# ADC.net
KiCad netlist of a schematic drawn in Altium Designer
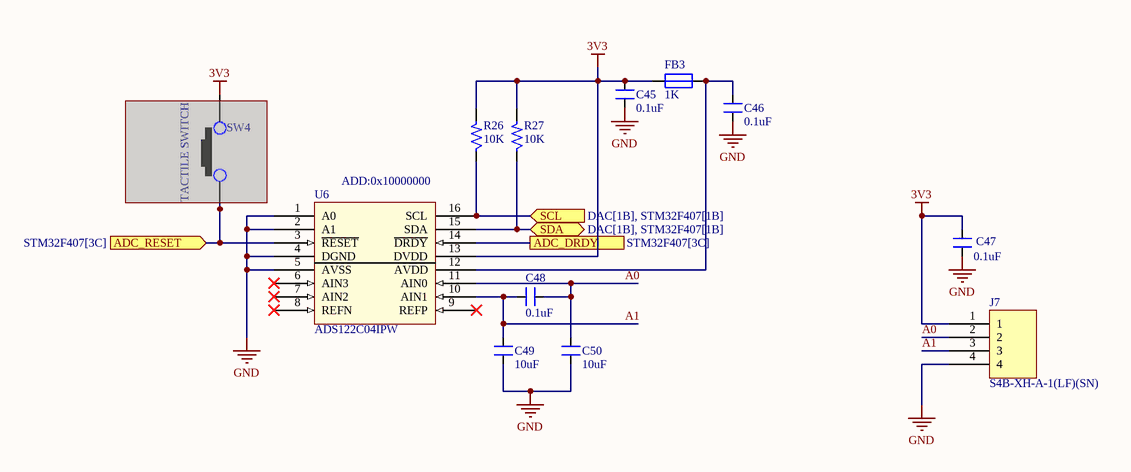
[diagram p0: ADC.SchDoc]

(export (version "E")
  (design (tool "Eeschema 10.0.6"))
  (components
    (comp (ref "C45")
      (value "0.1uF")
      (footprint "CAP_0805")
      (description "0.1µF ±10% 50V Ceramic Capacitor X7R 0805 (2012 Metric)")
      (fields
        (field (name "MANUFACTURER") "Samsung")
        (field (name "MANUFACTURER PART NUMBER") "CL21B104KBCNNNC")
      )
      (libsource (lib "ESTEEMPCBLIB") (part "CAP_0.1uF-50V-10%-0805"))
    )
    (comp (ref "C46")
      (value "0.1uF")
      (footprint "CAP_0805")
      (description "0.1µF ±10% 50V Ceramic Capacitor X7R 0805 (2012 Metric)")
      (fields
        (field (name "MANUFACTURER") "Samsung")
        (field (name "MANUFACTURER PART NUMBER") "CL21B104KBCNNNC")
      )
      (libsource (lib "ESTEEMPCBLIB") (part "CAP_0.1uF-50V-10%-0805"))
    )
    (comp (ref "C47")
      (value "0.1uF")
      (footprint "CAP_0805")
      (description "0.1µF ±10% 50V Ceramic Capacitor X7R 0805 (2012 Metric)")
      (fields
        (field (name "MANUFACTURER") "Samsung")
        (field (name "MANUFACTURER PART NUMBER") "CL21B104KBCNNNC")
      )
      (libsource (lib "ESTEEMPCBLIB") (part "CAP_0.1uF-50V-10%-0805"))
    )
    (comp (ref "C48")
      (value "0.1uF")
      (footprint "CAP_0805")
      (description "0.1µF ±5% 50V Ceramic Capacitor X7R 0805 (2012 Metric)")
      (fields
        (field (name "MANUFACTURER") "AVX Corporation")
        (field (name "MANUFACTURER PART NUMBER") "08055C104JAT4A")
      )
      (libsource (lib "ESTEEMPCBLIB") (part "CAP_0.1uF-50V-5%-0805"))
    )
    (comp (ref "C49")
      (value "10uF")
      (footprint "CAP_1206")
      (description "10µF ±10% 50V Ceramic Capacitor X7R 1206 (3216 Metric)")
      (fields
        (field (name "MANUFACTURER") "KEMET")
        (field (name "MANUFACTURER PART NUMBER") "CL31B106KBHNNNE")
      )
      (libsource (lib "ESTEEMPCBLIB") (part "CAP_10uF-50V-10%-1206"))
    )
    (comp (ref "C50")
      (value "10uF")
      (footprint "CAP_1206")
      (description "10µF ±10% 50V Ceramic Capacitor X7R 1206 (3216 Metric)")
      (fields
        (field (name "MANUFACTURER") "KEMET")
        (field (name "MANUFACTURER PART NUMBER") "CL31B106KBHNNNE")
      )
      (libsource (lib "ESTEEMPCBLIB") (part "CAP_10uF-50V-10%-1206"))
    )
    (comp (ref "FB3")
      (value "1K")
      (footprint "IND_0805")
      (description "1 kOhms @ 100MHz 1 Power Line Ferrite Bead 0805 (2012 Metric) 1.6A")
      (fields
        (field (name "MANUFACTURER") "Laird")
        (field (name "MANUFACTURER PART NUMBER") "BLM21SP102SH1D")
      )
      (libsource (lib "ESTEEMPCBLIB") (part "FB_1K-100MHZ-1.6A-0805"))
    )
    (comp (ref "J7")
      (value "S4B-XH-A-1(LF)(SN)")
      (footprint "CON4_100_S4B-XH-A_TH_RA")
      (description "4 Pins, 1 Row 2.54mm Pitch, right angle Connector, male")
      (fields (field (name "MANUFACTURER") "Wurth Electronics") (field (name "MATING PART NUMBER") "XHP-4"))
      (libsource (lib "ESTEEMPCBLIB") (part "CON-PLG_4X1-100-RA-TH"))
    )
    (comp (ref "R26")
      (value "10K")
      (footprint "RES_0603")
      (description "10 kOhms ±1% 0.1W, 1/10W Chip Resistor 0603 (1608 Metric) Automotive AEC-Q200 Thick Film")
      (fields (field (name "MANUFACTURER") "Walsin") (field (name "MANUFACTURER PART NUMBER") "WR06X1002FTL"))
      (libsource (lib "ESTEEMPCBLIB") (part "RES_10K-0.1W-1%-0603"))
    )
    (comp (ref "R27")
      (value "10K")
      (footprint "RES_0603")
      (description "10 kOhms ±1% 0.1W, 1/10W Chip Resistor 0603 (1608 Metric) Automotive AEC-Q200 Thick Film")
      (fields (field (name "MANUFACTURER") "Walsin") (field (name "MANUFACTURER PART NUMBER") "WR06X1002FTL"))
      (libsource (lib "ESTEEMPCBLIB") (part "RES_10K-0.1W-1%-0603"))
    )
    (comp (ref "SW4")
      (value "TACTILE SWITCH")
      (footprint "SW_342_SMD")
      (description "Tactile Switch SPST-NO Top Actuated Surface Mount")
      (fields
        (field (name "MANUFACTURER") "ITT C&K")
        (field (name "MANUFACTURER PART NUMBER") "RS-282G05A3-SMRT")
      )
      (libsource (lib "ESTEEMPCBLIB") (part "SW1_RS-282G05A3-SMRT-SMD"))
    )
    (comp (ref "U6")
      (value "ADS122C04IPW")
      (footprint "TSSOP16_25-59_294_54X14_SMT")
      (description "24 Bit Analog to Digital Converter 4 Input 1 Sigma-Delta 16-TSSOP")
      (fields (field (name "MANUFACTURER") "Texas Instruments"))
      (libsource (lib "ESTEEMPCBLIB") (part "IC_ADS122C04IPW"))
    )
  )
  (nets
    (net (code "1") (name "/A0") (class "Default")
      (node (ref "C48") (pin "1") (pinfunction "1_1") (pintype "passive"))
      (node (ref "C50") (pin "2") (pinfunction "2_2") (pintype "passive"))
      (node (ref "J7") (pin "2") (pinfunction "2_2") (pintype "passive"))
      (node (ref "U6") (pin "11") (pinfunction "AIN0_11") (pintype "input"))
    )
    (net (code "2") (name "/A1") (class "Default")
      (node (ref "C48") (pin "2") (pinfunction "2_2") (pintype "passive"))
      (node (ref "C49") (pin "2") (pinfunction "2_2") (pintype "passive"))
      (node (ref "J7") (pin "3") (pinfunction "3_3") (pintype "passive"))
      (node (ref "U6") (pin "10") (pinfunction "AIN1_10") (pintype "input"))
    )
    (net (code "3") (name "/ADC_DRDY") (class "Default")
      (node (ref "U6") (pin "14") (pinfunction "DRDY_14") (pintype "input"))
    )
    (net (code "4") (name "/ADC_RESET") (class "Default")
      (node (ref "SW4") (pin "1") (pinfunction "1_1") (pintype "passive"))
      (node (ref "U6") (pin "3") (pinfunction "RESET_3") (pintype "input"))
    )
    (net (code "5") (name "/SCL") (class "Default")
      (node (ref "R26") (pin "1") (pinfunction "1_1") (pintype "passive"))
      (node (ref "U6") (pin "16") (pinfunction "SCL_16") (pintype "open_collector"))
    )
    (net (code "6") (name "/SDA") (class "Default")
      (node (ref "R27") (pin "1") (pinfunction "1_1") (pintype "passive"))
      (node (ref "U6") (pin "15") (pinfunction "SDA_15") (pintype "open_collector"))
    )
    (net (code "7") (name "3V3") (class "Default")
      (node (ref "C45") (pin "2") (pinfunction "2_2") (pintype "passive"))
      (node (ref "C47") (pin "2") (pinfunction "2_2") (pintype "passive"))
      (node (ref "FB3") (pin "2") (pinfunction "2_2") (pintype "passive"))
      (node (ref "J7") (pin "1") (pinfunction "1_1") (pintype "passive"))
      (node (ref "R26") (pin "2") (pinfunction "2_2") (pintype "passive"))
      (node (ref "R27") (pin "2") (pinfunction "2_2") (pintype "passive"))
      (node (ref "SW4") (pin "2") (pinfunction "2_2") (pintype "passive"))
      (node (ref "U6") (pin "13") (pinfunction "DVDD_13") (pintype "power_in"))
    )
    (net (code "8") (name "GND") (class "Default")
      (node (ref "C45") (pin "1") (pinfunction "1_1") (pintype "passive"))
      (node (ref "C46") (pin "1") (pinfunction "1_1") (pintype "passive"))
      (node (ref "C47") (pin "1") (pinfunction "1_1") (pintype "passive"))
      (node (ref "C49") (pin "1") (pinfunction "1_1") (pintype "passive"))
      (node (ref "C50") (pin "1") (pinfunction "1_1") (pintype "passive"))
      (node (ref "J7") (pin "4") (pinfunction "4_4") (pintype "passive"))
      (node (ref "U6") (pin "1") (pinfunction "A0_1") (pintype "passive"))
      (node (ref "U6") (pin "2") (pinfunction "A1_2") (pintype "passive"))
      (node (ref "U6") (pin "4") (pinfunction "DGND_4") (pintype "power_in"))
      (node (ref "U6") (pin "5") (pinfunction "AVSS_5") (pintype "power_in"))
    )
    (net (code "9") (name "Net-(U6-AVDD)") (class "Default")
      (node (ref "C46") (pin "2") (pinfunction "2_2") (pintype "passive"))
      (node (ref "FB3") (pin "1") (pinfunction "1_1") (pintype "passive"))
      (node (ref "U6") (pin "12") (pinfunction "AVDD_12") (pintype "power_in"))
    )
    (net (code "10") (name "unconnected-(U6-AIN2-Pad7)") (class "Default")
      (node (ref "U6") (pin "7") (pinfunction "AIN2_7") (pintype "input+no_connect"))
    )
    (net (code "11") (name "unconnected-(U6-AIN3-Pad6)") (class "Default")
      (node (ref "U6") (pin "6") (pinfunction "AIN3_6") (pintype "input+no_connect"))
    )
    (net (code "12") (name "unconnected-(U6-REFN-Pad8)") (class "Default")
      (node (ref "U6") (pin "8") (pinfunction "REFN_8") (pintype "input+no_connect"))
    )
    (net (code "13") (name "unconnected-(U6-REFP-Pad9)") (class "Default")
      (node (ref "U6") (pin "9") (pinfunction "REFP_9") (pintype "input+no_connect"))
    )
  )
)
